# PIC12F629.net
KiCad netlist of a schematic drawn in EAGLE
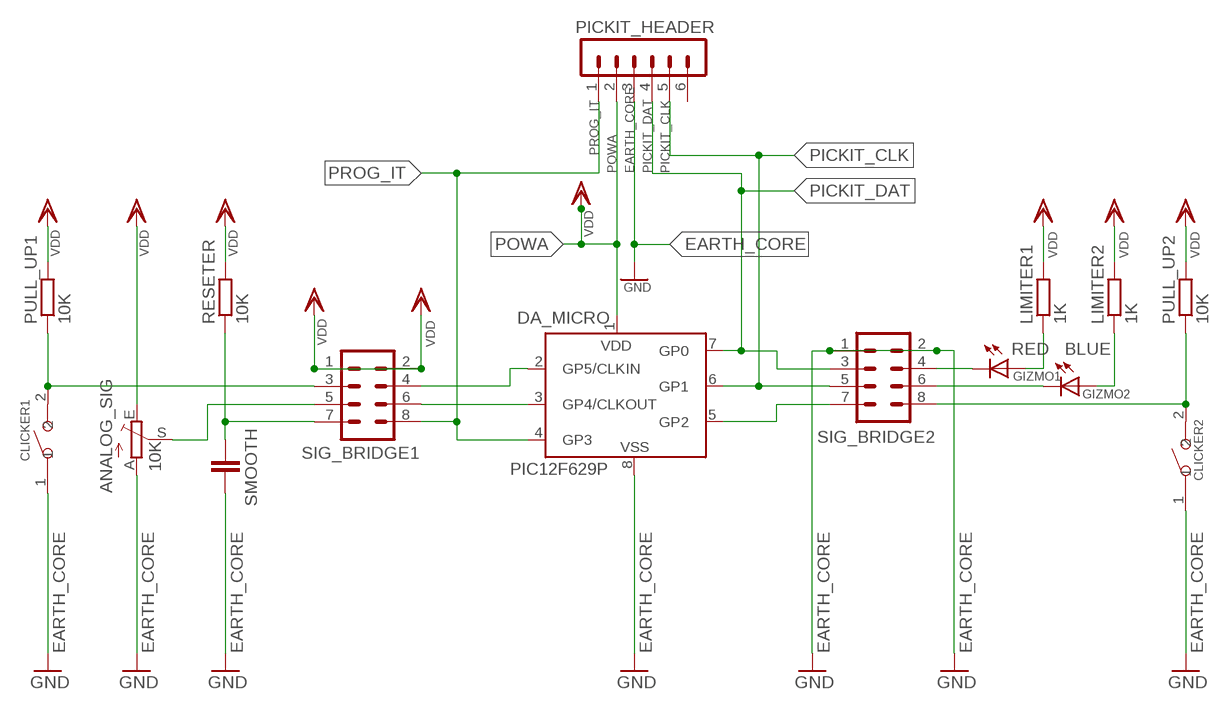
[diagram p0: schematic, sheet 1]

(export (version "E")
  (design (tool "Eeschema 10.0.6"))
  (components
    (comp (ref "ANALOG_SIG")
      (value "10K")
      (footprint "eagle-import:CA6V")
      (libsource (lib "eagle-import") (part "TRIM_EU-CA6V"))
    )
    (comp (ref "CLICKER1")
      (value "SMD-BUTTON(2P-6.0X3.0X2.5MM)-DHT-1163S")
      (footprint "eagle-import:SW2-4.0-6.0X3.0X2.5MM")
      (libsource (lib "eagle-import") (part "SMD-BUTTON(2P-6.0X3.0X2.5MM)-DHT-1163S"))
    )
    (comp (ref "CLICKER2")
      (value "SMD-BUTTON(2P-6.0X3.0X2.5MM)-DHT-1163S")
      (footprint "eagle-import:SW2-4.0-6.0X3.0X2.5MM")
      (libsource (lib "eagle-import") (part "SMD-BUTTON(2P-6.0X3.0X2.5MM)-DHT-1163S"))
    )
    (comp (ref "DA_MICRO")
      (value "PIC12F629P")
      (footprint "eagle-import:DIL8")
      (fields (field (name "MF") "MICROCHIP") (field (name "MPN") "PIC12F629-I/P"))
      (libsource (lib "eagle-import") (part "PIC12F6P29"))
    )
    (comp (ref "GIZMO1")
      (value "RED")
      (footprint "eagle-import:CHIP-LED0805")
      (libsource (lib "eagle-import") (part "LEDCHIP-LED0805"))
    )
    (comp (ref "GIZMO2")
      (value "BLUE")
      (footprint "eagle-import:CHIP-LED0805")
      (libsource (lib "eagle-import") (part "LEDCHIP-LED0805"))
    )
    (comp (ref "LIMITER1")
      (value "1K")
      (footprint "eagle-import:R0805")
      (libsource (lib "eagle-import") (part "R-EU_R0805"))
    )
    (comp (ref "LIMITER2")
      (value "1K")
      (footprint "eagle-import:R0805")
      (libsource (lib "eagle-import") (part "R-EU_R0805"))
    )
    (comp (ref "PICKIT_HEADER")
      (value "MA06-1")
      (footprint "eagle-import:MA06-1")
      (libsource (lib "eagle-import") (part "MA06-1"))
    )
    (comp (ref "PULL_UP1")
      (value "10K")
      (footprint "eagle-import:R0805")
      (libsource (lib "eagle-import") (part "R-EU_R0805"))
    )
    (comp (ref "PULL_UP2")
      (value "10K")
      (footprint "eagle-import:R0805")
      (libsource (lib "eagle-import") (part "R-EU_R0805"))
    )
    (comp (ref "RESETER")
      (value "10K")
      (footprint "eagle-import:R0805")
      (libsource (lib "eagle-import") (part "R-EU_R0805"))
    )
    (comp (ref "SIG_BRIDGE1")
      (value "MA04-2")
      (footprint "eagle-import:MA04-2")
      (libsource (lib "eagle-import") (part "MA04-2"))
    )
    (comp (ref "SIG_BRIDGE2")
      (value "MA04-2")
      (footprint "eagle-import:MA04-2")
      (libsource (lib "eagle-import") (part "MA04-2"))
    )
    (comp (ref "SMOOTH")
      (value "C-EUC0805K")
      (footprint "eagle-import:C0805K")
      (libsource (lib "eagle-import") (part "C-EUC0805K"))
    )
  )
  (nets
    (net (code "1") (name "EARTH_CORE") (class "Default")
      (node (ref "ANALOG_SIG") (pin "A") (pinfunction "A_A") (pintype "passive"))
      (node (ref "CLICKER1") (pin "1") (pinfunction "1_1") (pintype "bidirectional"))
      (node (ref "CLICKER2") (pin "1") (pinfunction "1_1") (pintype "bidirectional"))
      (node (ref "DA_MICRO") (pin "8") (pinfunction "VSS_8") (pintype "power_in"))
      (node (ref "PICKIT_HEADER") (pin "3") (pinfunction "3_3") (pintype "passive"))
      (node (ref "SIG_BRIDGE2") (pin "1") (pinfunction "1_1") (pintype "passive"))
      (node (ref "SIG_BRIDGE2") (pin "2") (pinfunction "2_2") (pintype "passive"))
      (node (ref "SMOOTH") (pin "2") (pinfunction "2_2") (pintype "passive"))
    )
    (net (code "2") (name "Net-(ANALOG_SIG-PadS)") (class "Default")
      (node (ref "ANALOG_SIG") (pin "S") (pinfunction "S_S") (pintype "passive"))
      (node (ref "SIG_BRIDGE1") (pin "5") (pinfunction "5_5") (pintype "passive"))
    )
    (net (code "3") (name "Net-(CLICKER1-Pad2)") (class "Default")
      (node (ref "CLICKER1") (pin "2") (pinfunction "2_2") (pintype "bidirectional"))
      (node (ref "PULL_UP1") (pin "1") (pinfunction "1_1") (pintype "passive"))
      (node (ref "SIG_BRIDGE1") (pin "3") (pinfunction "3_3") (pintype "passive"))
    )
    (net (code "4") (name "Net-(CLICKER2-Pad2)") (class "Default")
      (node (ref "CLICKER2") (pin "2") (pinfunction "2_2") (pintype "bidirectional"))
      (node (ref "PULL_UP2") (pin "1") (pinfunction "1_1") (pintype "passive"))
      (node (ref "SIG_BRIDGE2") (pin "8") (pinfunction "8_8") (pintype "passive"))
    )
    (net (code "5") (name "Net-(DA_MICRO-GP2)") (class "Default")
      (node (ref "DA_MICRO") (pin "5") (pinfunction "GP2_5") (pintype "bidirectional"))
      (node (ref "SIG_BRIDGE2") (pin "7") (pinfunction "7_7") (pintype "passive"))
    )
    (net (code "6") (name "Net-(DA_MICRO-GP4{slash}CLKOUT)") (class "Default")
      (node (ref "DA_MICRO") (pin "3") (pinfunction "GP4/CLKOUT_3") (pintype "bidirectional"))
      (node (ref "SIG_BRIDGE1") (pin "6") (pinfunction "6_6") (pintype "passive"))
    )
    (net (code "7") (name "Net-(DA_MICRO-GP5{slash}CLKIN)") (class "Default")
      (node (ref "DA_MICRO") (pin "2") (pinfunction "GP5/CLKIN_2") (pintype "bidirectional"))
      (node (ref "SIG_BRIDGE1") (pin "4") (pinfunction "4_4") (pintype "passive"))
    )
    (net (code "8") (name "Net-(GIZMO1-PadA)") (class "Default")
      (node (ref "GIZMO1") (pin "A") (pinfunction "A_A") (pintype "passive"))
      (node (ref "LIMITER1") (pin "1") (pinfunction "1_1") (pintype "passive"))
    )
    (net (code "9") (name "Net-(GIZMO1-PadC)") (class "Default")
      (node (ref "GIZMO1") (pin "C") (pinfunction "C_C") (pintype "passive"))
      (node (ref "SIG_BRIDGE2") (pin "4") (pinfunction "4_4") (pintype "passive"))
    )
    (net (code "10") (name "Net-(GIZMO2-PadA)") (class "Default")
      (node (ref "GIZMO2") (pin "A") (pinfunction "A_A") (pintype "passive"))
      (node (ref "LIMITER2") (pin "1") (pinfunction "1_1") (pintype "passive"))
    )
    (net (code "11") (name "Net-(GIZMO2-PadC)") (class "Default")
      (node (ref "GIZMO2") (pin "C") (pinfunction "C_C") (pintype "passive"))
      (node (ref "SIG_BRIDGE2") (pin "6") (pinfunction "6_6") (pintype "passive"))
    )
    (net (code "12") (name "Net-(RESETER-Pad1)") (class "Default")
      (node (ref "RESETER") (pin "1") (pinfunction "1_1") (pintype "passive"))
      (node (ref "SIG_BRIDGE1") (pin "7") (pinfunction "7_7") (pintype "passive"))
      (node (ref "SMOOTH") (pin "1") (pinfunction "1_1") (pintype "passive"))
    )
    (net (code "13") (name "PICKIT_CLK") (class "Default")
      (node (ref "DA_MICRO") (pin "6") (pinfunction "GP1_6") (pintype "bidirectional"))
      (node (ref "PICKIT_HEADER") (pin "5") (pinfunction "5_5") (pintype "passive"))
      (node (ref "SIG_BRIDGE2") (pin "5") (pinfunction "5_5") (pintype "passive"))
    )
    (net (code "14") (name "PICKIT_DAT") (class "Default")
      (node (ref "DA_MICRO") (pin "7") (pinfunction "GP0_7") (pintype "bidirectional"))
      (node (ref "PICKIT_HEADER") (pin "4") (pinfunction "4_4") (pintype "passive"))
      (node (ref "SIG_BRIDGE2") (pin "3") (pinfunction "3_3") (pintype "passive"))
    )
    (net (code "15") (name "POWA") (class "Default")
      (node (ref "ANALOG_SIG") (pin "E") (pinfunction "E_E") (pintype "passive"))
      (node (ref "DA_MICRO") (pin "1") (pinfunction "VDD_1") (pintype "power_in"))
      (node (ref "LIMITER1") (pin "2") (pinfunction "2_2") (pintype "passive"))
      (node (ref "LIMITER2") (pin "2") (pinfunction "2_2") (pintype "passive"))
      (node (ref "PICKIT_HEADER") (pin "2") (pinfunction "2_2") (pintype "passive"))
      (node (ref "PULL_UP1") (pin "2") (pinfunction "2_2") (pintype "passive"))
      (node (ref "PULL_UP2") (pin "2") (pinfunction "2_2") (pintype "passive"))
      (node (ref "RESETER") (pin "2") (pinfunction "2_2") (pintype "passive"))
      (node (ref "SIG_BRIDGE1") (pin "1") (pinfunction "1_1") (pintype "passive"))
      (node (ref "SIG_BRIDGE1") (pin "2") (pinfunction "2_2") (pintype "passive"))
    )
    (net (code "16") (name "PROG_IT") (class "Default")
      (node (ref "DA_MICRO") (pin "4") (pinfunction "GP3_4") (pintype "input"))
      (node (ref "PICKIT_HEADER") (pin "1") (pinfunction "1_1") (pintype "passive"))
      (node (ref "SIG_BRIDGE1") (pin "8") (pinfunction "8_8") (pintype "passive"))
    )
    (net (code "17") (name "unconnected-(PICKIT_HEADER-Pad6)") (class "Default")
      (node (ref "PICKIT_HEADER") (pin "6") (pinfunction "6_6") (pintype "passive"))
    )
  )
)
